# analog-interface.net
KiCad netlist of a schematic drawn in EAGLE
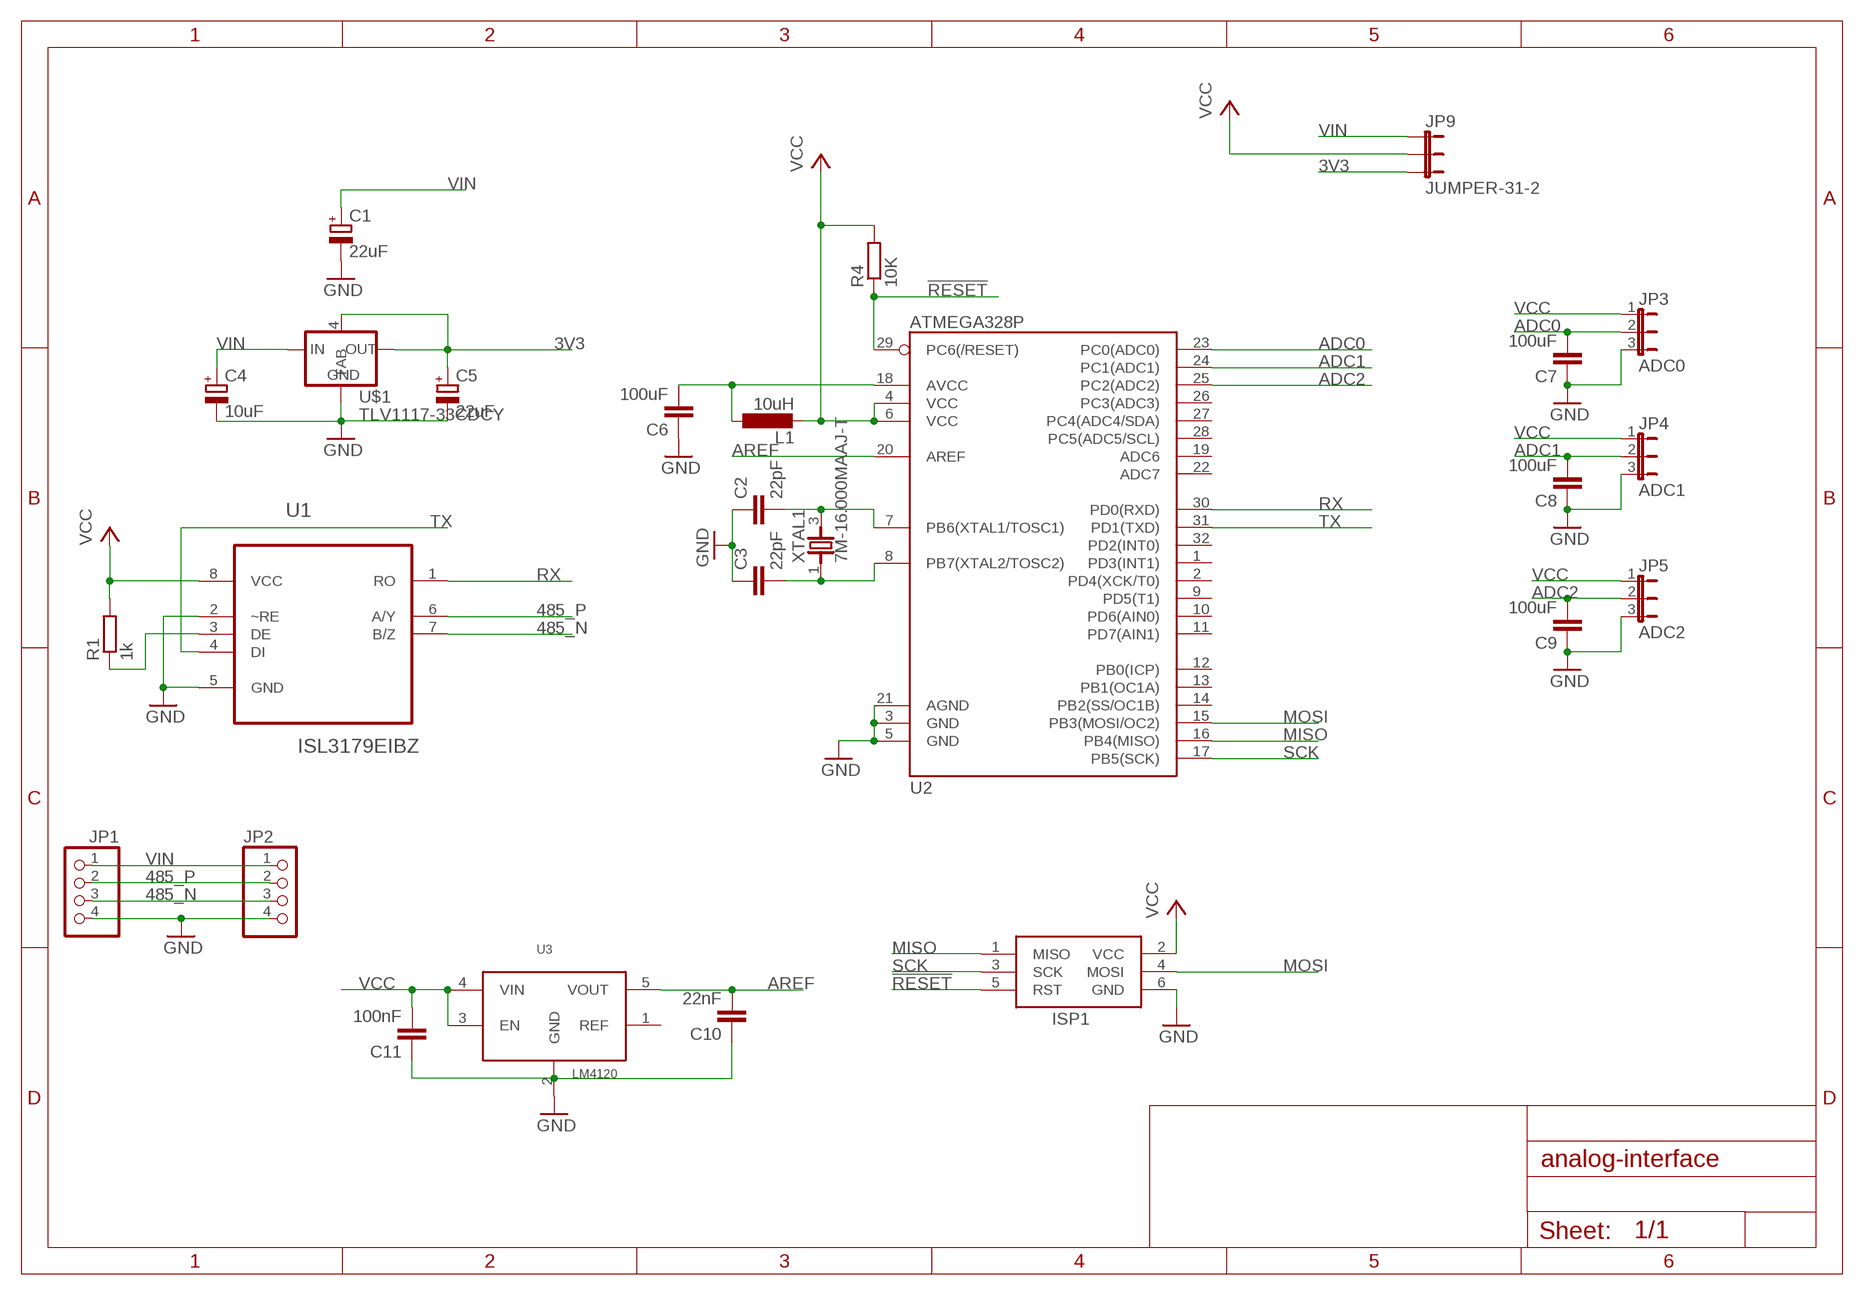
[diagram p0: schematic, sheet 1]

(export (version "E")
  (design (tool "Eeschema 10.0.6"))
  (components
    (comp (ref "C1")
      (value "22uF")
      (footprint "eagle-import:A_3216-18R")
      (libsource (lib "eagle-import") (part "CPOL-EUA/3216-18R"))
    )
    (comp (ref "C2")
      (value "22pF")
      (footprint "eagle-import:C0805")
      (libsource (lib "eagle-import") (part "C-EUC0805"))
    )
    (comp (ref "C3")
      (value "22pF")
      (footprint "eagle-import:C0805")
      (libsource (lib "eagle-import") (part "C-EUC0805"))
    )
    (comp (ref "C4")
      (value "10uF")
      (footprint "eagle-import:A_3216-18R")
      (libsource (lib "eagle-import") (part "CPOL-EUA/3216-18R"))
    )
    (comp (ref "C5")
      (value "22uF")
      (footprint "eagle-import:A_3216-18R")
      (libsource (lib "eagle-import") (part "CPOL-EUA/3216-18R"))
    )
    (comp (ref "C6")
      (value "100uF")
      (footprint "eagle-import:C0805")
      (libsource (lib "eagle-import") (part "C-EUC0805"))
    )
    (comp (ref "C7")
      (value "100uF")
      (footprint "eagle-import:C0805")
      (libsource (lib "eagle-import") (part "C-EUC0805"))
    )
    (comp (ref "C8")
      (value "100uF")
      (footprint "eagle-import:C0805")
      (libsource (lib "eagle-import") (part "C-EUC0805"))
    )
    (comp (ref "C9")
      (value "100uF")
      (footprint "eagle-import:C0805")
      (libsource (lib "eagle-import") (part "C-EUC0805"))
    )
    (comp (ref "C10")
      (value "22nF")
      (footprint "eagle-import:C0805")
      (libsource (lib "eagle-import") (part "C-EUC0805"))
    )
    (comp (ref "C11")
      (value "100nF")
      (footprint "eagle-import:C0805")
      (libsource (lib "eagle-import") (part "C-EUC0805"))
    )
    (comp (ref "ISP1")
      (value "AVRISP-6")
      (footprint "eagle-import:AVRISP")
      (libsource (lib "eagle-import") (part "AVRISP-6"))
    )
    (comp (ref "JP1")
      (value "PINHD-1X4")
      (footprint "eagle-import:1X04")
      (libsource (lib "eagle-import") (part "PINHD-1X4"))
    )
    (comp (ref "JP2")
      (value "PINHD-1X4")
      (footprint "eagle-import:1X04")
      (libsource (lib "eagle-import") (part "PINHD-1X4"))
    )
    (comp (ref "JP3")
      (value "ADC0")
      (footprint "eagle-import:3-MOLEX")
      (libsource (lib "eagle-import") (part "3-PIN-MOLEX"))
    )
    (comp (ref "JP4")
      (value "ADC1")
      (footprint "eagle-import:3-MOLEX")
      (libsource (lib "eagle-import") (part "3-PIN-MOLEX"))
    )
    (comp (ref "JP5")
      (value "ADC2")
      (footprint "eagle-import:3-MOLEX")
      (libsource (lib "eagle-import") (part "3-PIN-MOLEX"))
    )
    (comp (ref "JP9")
      (value "JUMPER-31-2")
      (footprint "eagle-import:SJ_3_PASTE1&2")
      (libsource (lib "eagle-import") (part "JUMPER-31-2"))
    )
    (comp (ref "L1")
      (value "10uH")
      (footprint "eagle-import:L3216C")
      (libsource (lib "eagle-import") (part "L-EUL3216C"))
    )
    (comp (ref "R1")
      (value "1k")
      (footprint "eagle-import:R0805")
      (libsource (lib "eagle-import") (part "R-EU_R0805"))
    )
    (comp (ref "R4")
      (value "10K")
      (footprint "eagle-import:R0805")
      (libsource (lib "eagle-import") (part "R-EU_R0805"))
    )
    (comp (ref "U$1")
      (value "TLV1117-33CDCY")
      (footprint "eagle-import:SOT223")
      (libsource (lib "eagle-import") (part "TLV1117-33CDCY"))
    )
    (comp (ref "U1")
      (value "ISL3179EIBZ")
      (footprint "eagle-import:SOIC127P600X175-8N")
      (libsource (lib "eagle-import") (part "ISL3179EIBZ"))
    )
    (comp (ref "U2")
      (value "ATMEGA328P")
      (footprint "eagle-import:TQFP32-08")
      (libsource (lib "eagle-import") (part "ATMEGA328_SMT"))
    )
    (comp (ref "U3")
      (value "LM4120")
      (footprint "eagle-import:SOT23-5")
      (libsource (lib "eagle-import") (part "LM4120"))
    )
    (comp (ref "XTAL1")
      (value "7M-16.000MAAJ-T")
      (footprint "eagle-import:TXC_7M-16.000MAAJ-T")
      (fields (field (name "MPN") "7M-16.000MAAJ-T "))
      (libsource (lib "eagle-import") (part "7M-16.000MAAJ-T"))
    )
  )
  (nets
    (net (code "1") (name "/3V3") (class "Default")
      (node (ref "C5") (pin "+") (pinfunction "+_+") (pintype "passive"))
      (node (ref "JP9") (pin "3") (pinfunction "3_3") (pintype "passive"))
      (node (ref "U$1") (pin "2") (pinfunction "OUT_2") (pintype "passive"))
      (node (ref "U$1") (pin "4") (pinfunction "TAB_4") (pintype "passive"))
    )
    (net (code "2") (name "/485_N") (class "Default")
      (node (ref "JP1") (pin "3") (pinfunction "3_3") (pintype "passive"))
      (node (ref "JP2") (pin "3") (pinfunction "3_3") (pintype "passive"))
      (node (ref "U1") (pin "7") (pinfunction "B/Z_7") (pintype "bidirectional"))
    )
    (net (code "3") (name "/485_P") (class "Default")
      (node (ref "JP1") (pin "2") (pinfunction "2_2") (pintype "passive"))
      (node (ref "JP2") (pin "2") (pinfunction "2_2") (pintype "passive"))
      (node (ref "U1") (pin "6") (pinfunction "A/Y_6") (pintype "bidirectional"))
    )
    (net (code "4") (name "/ADC0") (class "Default")
      (node (ref "C7") (pin "2") (pinfunction "2_2") (pintype "passive"))
      (node (ref "JP3") (pin "2") (pinfunction "2_2") (pintype "passive"))
      (node (ref "U2") (pin "23") (pinfunction "PC0(ADC0)_23") (pintype "bidirectional"))
    )
    (net (code "5") (name "/ADC1") (class "Default")
      (node (ref "C8") (pin "2") (pinfunction "2_2") (pintype "passive"))
      (node (ref "JP4") (pin "2") (pinfunction "2_2") (pintype "passive"))
      (node (ref "U2") (pin "24") (pinfunction "PC1(ADC1)_24") (pintype "bidirectional"))
    )
    (net (code "6") (name "/ADC2") (class "Default")
      (node (ref "C9") (pin "2") (pinfunction "2_2") (pintype "passive"))
      (node (ref "JP5") (pin "2") (pinfunction "2_2") (pintype "passive"))
      (node (ref "U2") (pin "25") (pinfunction "PC2(ADC2)_25") (pintype "bidirectional"))
    )
    (net (code "7") (name "/AREF") (class "Default")
      (node (ref "C10") (pin "2") (pinfunction "2_2") (pintype "passive"))
      (node (ref "U2") (pin "20") (pinfunction "AREF_20") (pintype "bidirectional"))
      (node (ref "U3") (pin "5") (pinfunction "VOUT_5") (pintype "bidirectional"))
    )
    (net (code "8") (name "/MISO") (class "Default")
      (node (ref "ISP1") (pin "1") (pinfunction "MISO_1") (pintype "input"))
      (node (ref "U2") (pin "16") (pinfunction "PB4(MISO)_16") (pintype "bidirectional"))
    )
    (net (code "9") (name "/MOSI") (class "Default")
      (node (ref "ISP1") (pin "4") (pinfunction "MOSI_4") (pintype "output"))
      (node (ref "U2") (pin "15") (pinfunction "PB3(MOSI/OC2)_15") (pintype "bidirectional"))
    )
    (net (code "10") (name "/RX") (class "Default")
      (node (ref "U1") (pin "1") (pinfunction "RO_1") (pintype "output"))
      (node (ref "U2") (pin "30") (pinfunction "PD0(RXD)_30") (pintype "bidirectional"))
    )
    (net (code "11") (name "/SCK") (class "Default")
      (node (ref "ISP1") (pin "3") (pinfunction "SCK_3") (pintype "output"))
      (node (ref "U2") (pin "17") (pinfunction "PB5(SCK)_17") (pintype "bidirectional"))
    )
    (net (code "12") (name "/TX") (class "Default")
      (node (ref "U1") (pin "4") (pinfunction "DI_4") (pintype "input"))
      (node (ref "U2") (pin "31") (pinfunction "PD1(TXD)_31") (pintype "bidirectional"))
    )
    (net (code "13") (name "/VIN") (class "Default")
      (node (ref "C1") (pin "+") (pinfunction "+_+") (pintype "passive"))
      (node (ref "C4") (pin "+") (pinfunction "+_+") (pintype "passive"))
      (node (ref "JP1") (pin "1") (pinfunction "1_1") (pintype "passive"))
      (node (ref "JP2") (pin "1") (pinfunction "1_1") (pintype "passive"))
      (node (ref "JP9") (pin "1") (pinfunction "1_1") (pintype "passive"))
      (node (ref "U$1") (pin "3") (pinfunction "IN_3") (pintype "input"))
    )
    (net (code "14") (name "/~{RESET}") (class "Default")
      (node (ref "ISP1") (pin "5") (pinfunction "RST_5") (pintype "output"))
      (node (ref "R4") (pin "1") (pinfunction "1_1") (pintype "passive"))
      (node (ref "U2") (pin "29") (pinfunction "PC6(/RESET)_29") (pintype "bidirectional"))
    )
    (net (code "15") (name "GND") (class "Default")
      (node (ref "C1") (pin "-") (pinfunction "-_-") (pintype "passive"))
      (node (ref "C2") (pin "1") (pinfunction "1_1") (pintype "passive"))
      (node (ref "C3") (pin "1") (pinfunction "1_1") (pintype "passive"))
      (node (ref "C4") (pin "-") (pinfunction "-_-") (pintype "passive"))
      (node (ref "C5") (pin "-") (pinfunction "-_-") (pintype "passive"))
      (node (ref "C6") (pin "1") (pinfunction "1_1") (pintype "passive"))
      (node (ref "C7") (pin "1") (pinfunction "1_1") (pintype "passive"))
      (node (ref "C8") (pin "1") (pinfunction "1_1") (pintype "passive"))
      (node (ref "C9") (pin "1") (pinfunction "1_1") (pintype "passive"))
      (node (ref "ISP1") (pin "6") (pinfunction "GND_6") (pintype "power_in"))
      (node (ref "JP1") (pin "4") (pinfunction "4_4") (pintype "passive"))
      (node (ref "JP2") (pin "4") (pinfunction "4_4") (pintype "passive"))
      (node (ref "JP3") (pin "3") (pinfunction "3_3") (pintype "passive"))
      (node (ref "JP4") (pin "3") (pinfunction "3_3") (pintype "passive"))
      (node (ref "JP5") (pin "3") (pinfunction "3_3") (pintype "passive"))
      (node (ref "U$1") (pin "1") (pinfunction "GND_1") (pintype "input"))
      (node (ref "U1") (pin "2") (pinfunction "~{RE}_2") (pintype "input"))
      (node (ref "U1") (pin "5") (pinfunction "GND_5") (pintype "passive"))
      (node (ref "U2") (pin "21") (pinfunction "AGND_21") (pintype "bidirectional"))
      (node (ref "U2") (pin "3") (pinfunction "GND_3") (pintype "bidirectional"))
      (node (ref "U2") (pin "5") (pinfunction "GND_5") (pintype "bidirectional"))
      (node (ref "U3") (pin "2") (pinfunction "GND_2") (pintype "bidirectional"))
    )
    (net (code "16") (name "Net-(C10-Pad1)") (class "Default")
      (node (ref "C10") (pin "1") (pinfunction "1_1") (pintype "passive"))
      (node (ref "C11") (pin "1") (pinfunction "1_1") (pintype "passive"))
    )
    (net (code "17") (name "Net-(U1-DE)") (class "Default")
      (node (ref "R1") (pin "1") (pinfunction "1_1") (pintype "passive"))
      (node (ref "U1") (pin "3") (pinfunction "DE_3") (pintype "input"))
    )
    (net (code "18") (name "Net-(U2-AVCC)") (class "Default")
      (node (ref "C6") (pin "2") (pinfunction "2_2") (pintype "passive"))
      (node (ref "L1") (pin "1") (pinfunction "1_1") (pintype "passive"))
      (node (ref "U2") (pin "18") (pinfunction "AVCC_18") (pintype "bidirectional"))
    )
    (net (code "19") (name "Net-(U2-PB6(XTAL1{slash}TOSC1))") (class "Default")
      (node (ref "C2") (pin "2") (pinfunction "2_2") (pintype "passive"))
      (node (ref "U2") (pin "7") (pinfunction "PB6(XTAL1/TOSC1)_7") (pintype "bidirectional"))
      (node (ref "XTAL1") (pin "3") (pinfunction "3_3") (pintype "passive"))
    )
    (net (code "20") (name "Net-(U2-PB7(XTAL2{slash}TOSC2))") (class "Default")
      (node (ref "C3") (pin "2") (pinfunction "2_2") (pintype "passive"))
      (node (ref "U2") (pin "8") (pinfunction "PB7(XTAL2/TOSC2)_8") (pintype "bidirectional"))
      (node (ref "XTAL1") (pin "1") (pinfunction "1_1") (pintype "passive"))
    )
    (net (code "21") (name "VCC") (class "Default")
      (node (ref "C11") (pin "2") (pinfunction "2_2") (pintype "passive"))
      (node (ref "ISP1") (pin "2") (pinfunction "VCC_2") (pintype "power_in"))
      (node (ref "JP3") (pin "1") (pinfunction "1_1") (pintype "passive"))
      (node (ref "JP4") (pin "1") (pinfunction "1_1") (pintype "passive"))
      (node (ref "JP5") (pin "1") (pinfunction "1_1") (pintype "passive"))
      (node (ref "JP9") (pin "2") (pinfunction "2_2") (pintype "passive"))
      (node (ref "L1") (pin "2") (pinfunction "2_2") (pintype "passive"))
      (node (ref "R1") (pin "2") (pinfunction "2_2") (pintype "passive"))
      (node (ref "R4") (pin "2") (pinfunction "2_2") (pintype "passive"))
      (node (ref "U1") (pin "8") (pinfunction "VCC_8") (pintype "power_in"))
      (node (ref "U2") (pin "4") (pinfunction "VCC_4") (pintype "bidirectional"))
      (node (ref "U2") (pin "6") (pinfunction "VCC_6") (pintype "bidirectional"))
      (node (ref "U3") (pin "3") (pinfunction "EN_3") (pintype "bidirectional"))
      (node (ref "U3") (pin "4") (pinfunction "VIN_4") (pintype "bidirectional"))
    )
    (net (code "22") (name "unconnected-(U2-ADC6-Pad19)") (class "Default")
      (node (ref "U2") (pin "19") (pinfunction "ADC6_19") (pintype "bidirectional"))
    )
    (net (code "23") (name "unconnected-(U2-ADC7-Pad22)") (class "Default")
      (node (ref "U2") (pin "22") (pinfunction "ADC7_22") (pintype "bidirectional"))
    )
    (net (code "24") (name "unconnected-(U2-PB0(ICP)-Pad12)") (class "Default")
      (node (ref "U2") (pin "12") (pinfunction "PB0(ICP)_12") (pintype "bidirectional"))
    )
    (net (code "25") (name "unconnected-(U2-PB1(OC1A)-Pad13)") (class "Default")
      (node (ref "U2") (pin "13") (pinfunction "PB1(OC1A)_13") (pintype "bidirectional"))
    )
    (net (code "26") (name "unconnected-(U2-PB2(SS{slash}OC1B)-Pad14)") (class "Default")
      (node (ref "U2") (pin "14") (pinfunction "PB2(SS/OC1B)_14") (pintype "bidirectional"))
    )
    (net (code "27") (name "unconnected-(U2-PC3(ADC3)-Pad26)") (class "Default")
      (node (ref "U2") (pin "26") (pinfunction "PC3(ADC3)_26") (pintype "bidirectional"))
    )
    (net (code "28") (name "unconnected-(U2-PC4(ADC4{slash}SDA)-Pad27)") (class "Default")
      (node (ref "U2") (pin "27") (pinfunction "PC4(ADC4/SDA)_27") (pintype "bidirectional"))
    )
    (net (code "29") (name "unconnected-(U2-PC5(ADC5{slash}SCL)-Pad28)") (class "Default")
      (node (ref "U2") (pin "28") (pinfunction "PC5(ADC5/SCL)_28") (pintype "bidirectional"))
    )
    (net (code "30") (name "unconnected-(U2-PD2(INT0)-Pad32)") (class "Default")
      (node (ref "U2") (pin "32") (pinfunction "PD2(INT0)_32") (pintype "bidirectional"))
    )
    (net (code "31") (name "unconnected-(U2-PD3(INT1)-Pad1)") (class "Default")
      (node (ref "U2") (pin "1") (pinfunction "PD3(INT1)_1") (pintype "bidirectional"))
    )
    (net (code "32") (name "unconnected-(U2-PD4(XCK{slash}T0)-Pad2)") (class "Default")
      (node (ref "U2") (pin "2") (pinfunction "PD4(XCK/T0)_2") (pintype "bidirectional"))
    )
    (net (code "33") (name "unconnected-(U2-PD5(T1)-Pad9)") (class "Default")
      (node (ref "U2") (pin "9") (pinfunction "PD5(T1)_9") (pintype "bidirectional"))
    )
    (net (code "34") (name "unconnected-(U2-PD6(AIN0)-Pad10)") (class "Default")
      (node (ref "U2") (pin "10") (pinfunction "PD6(AIN0)_10") (pintype "bidirectional"))
    )
    (net (code "35") (name "unconnected-(U2-PD7(AIN1)-Pad11)") (class "Default")
      (node (ref "U2") (pin "11") (pinfunction "PD7(AIN1)_11") (pintype "bidirectional"))
    )
    (net (code "36") (name "unconnected-(U3-REF-Pad1)") (class "Default")
      (node (ref "U3") (pin "1") (pinfunction "REF_1") (pintype "bidirectional"))
    )
  )
)
